# ADC.net
KiCad netlist of a schematic drawn in Altium Designer
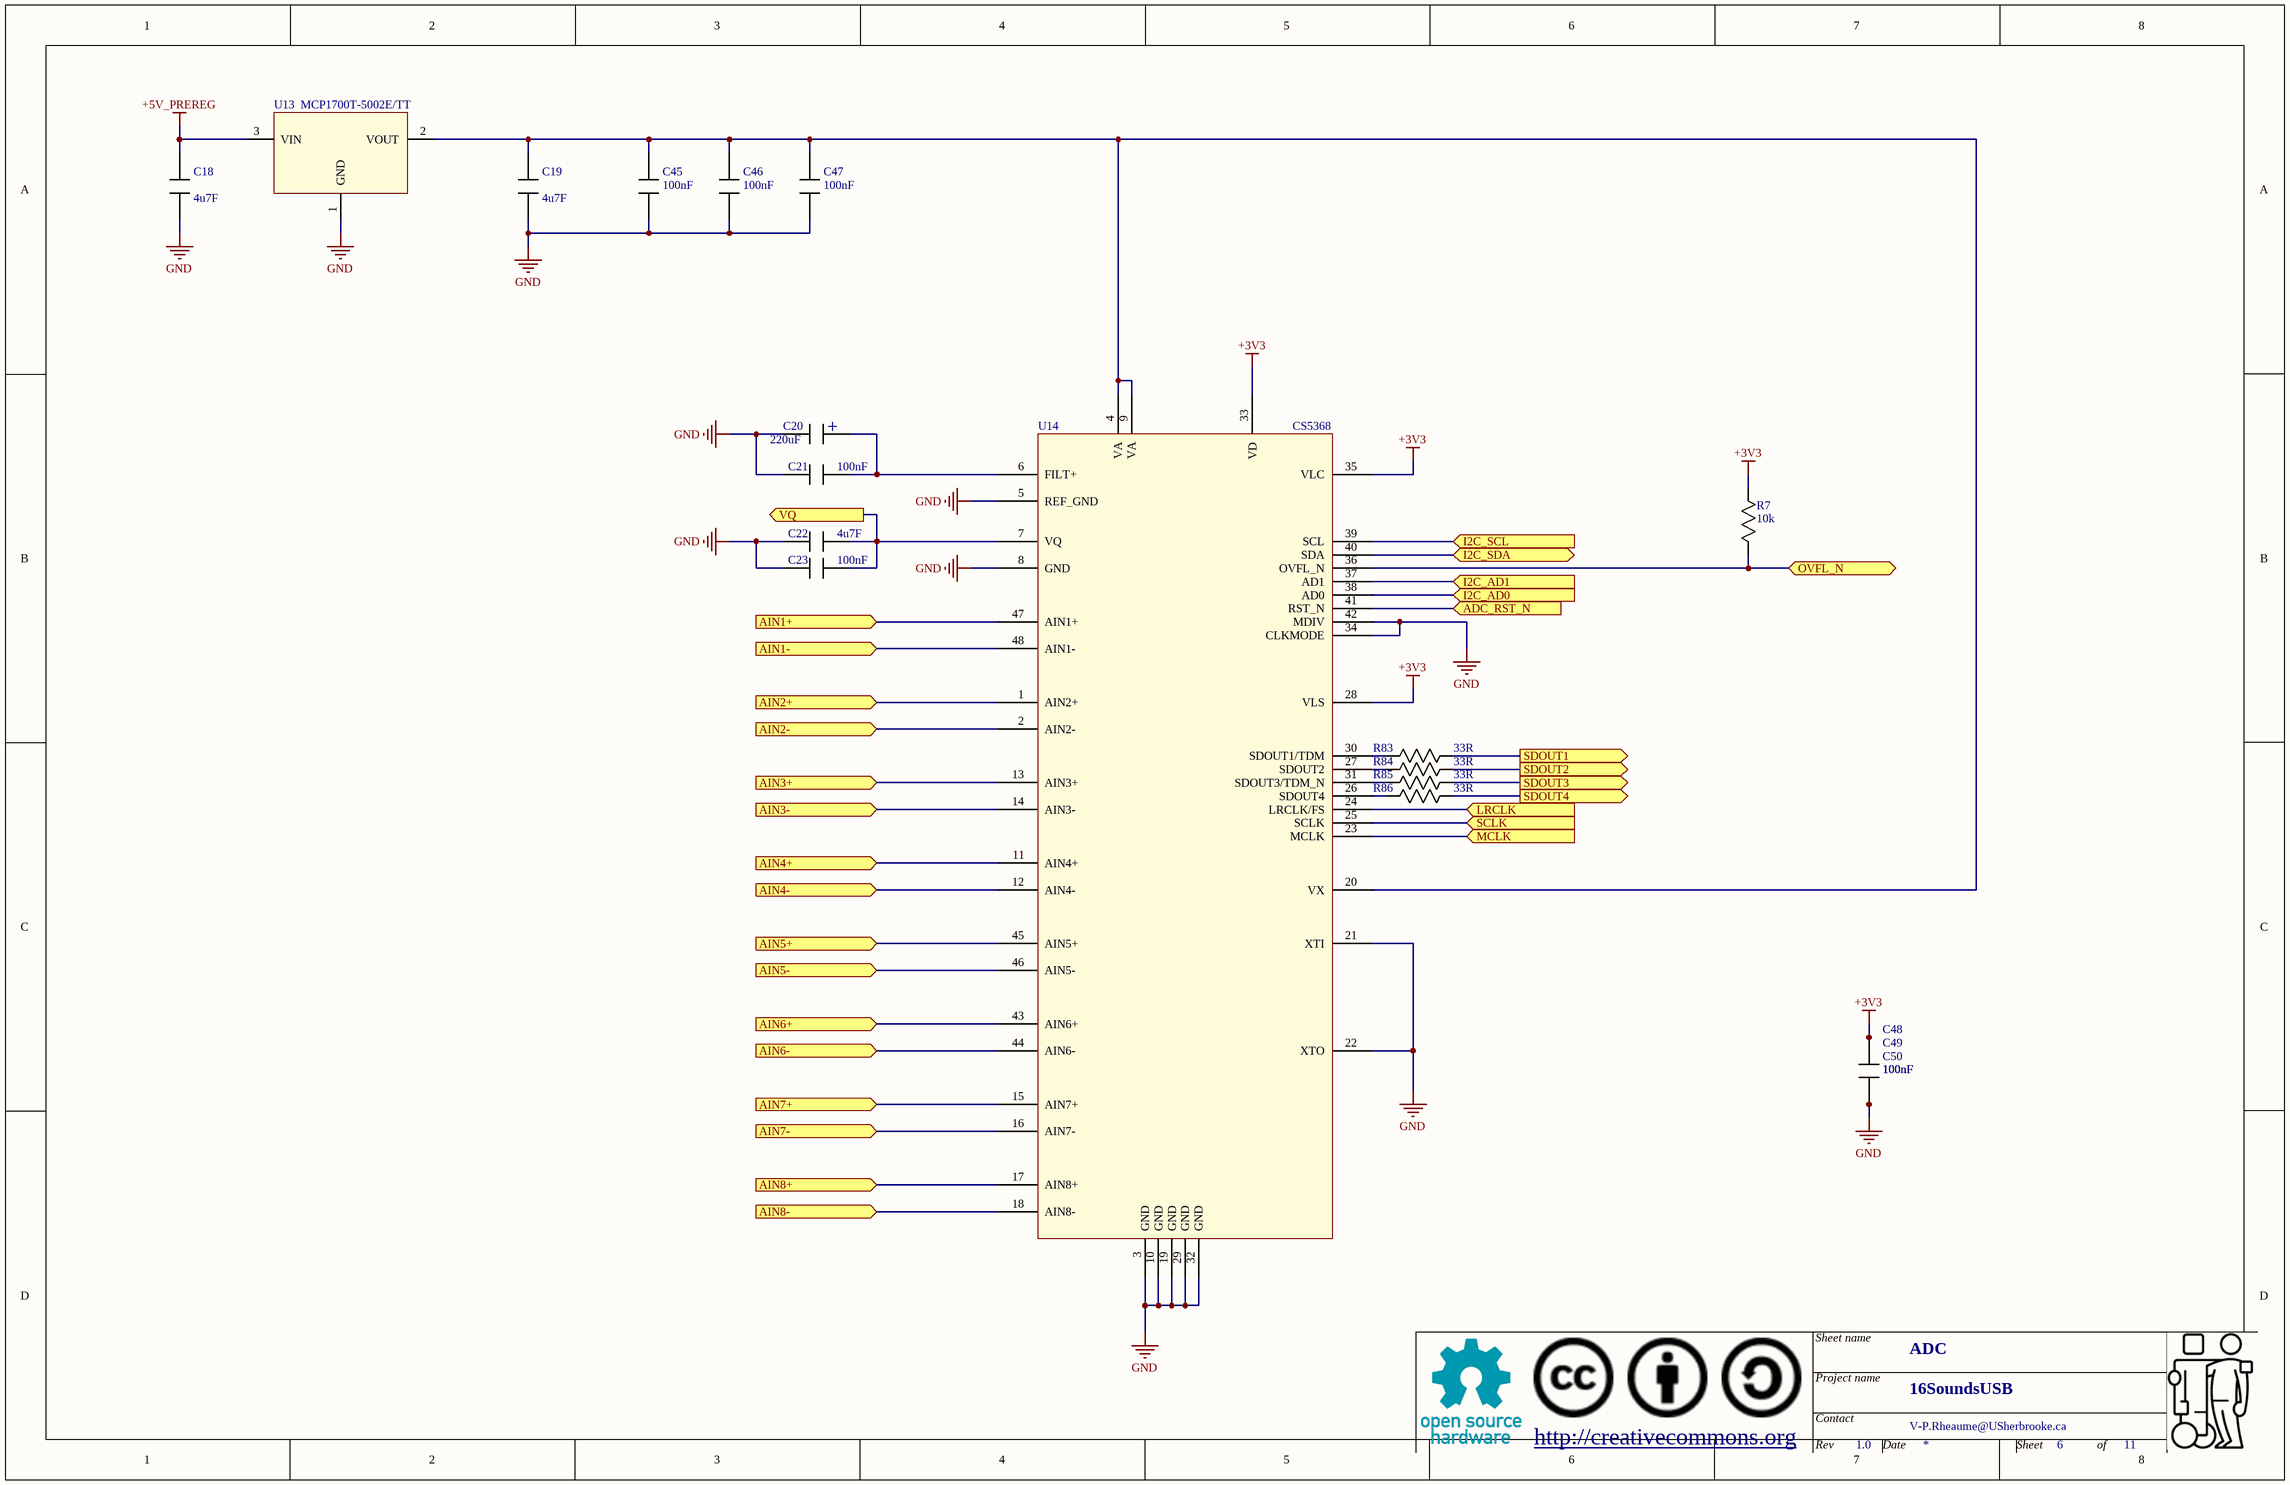
[diagram p0: ADC.SchDoc]

(export (version "E")
  (design (tool "Eeschema 10.0.6"))
  (components
    (comp (ref "C18")
      (value "4u7F")
      (footprint "0805")
      (description "Capacitor")
      (libsource (lib "INTER_2014") (part "Capacitor"))
    )
    (comp (ref "C19")
      (value "4u7F")
      (footprint "0805")
      (description "Capacitor")
      (libsource (lib "INTER_2014") (part "Capacitor"))
    )
    (comp (ref "C20")
      (value "220uF")
      (footprint "CAP_RAD_SMD_DIA315")
      (description "Capacitor")
      (fields (field (name "Comment") "Capacitor_Polarized"))
      (libsource (lib "INTER_2014") (part "Capacitor_Polarized"))
    )
    (comp (ref "C21")
      (value "100nF")
      (footprint "0603")
      (description "Capacitor")
      (libsource (lib "INTER_2014") (part "Capacitor"))
    )
    (comp (ref "C22")
      (value "4u7F")
      (footprint "0805")
      (description "Capacitor")
      (libsource (lib "INTER_2014") (part "Capacitor"))
    )
    (comp (ref "C23")
      (value "100nF")
      (footprint "0603")
      (description "Capacitor")
      (libsource (lib "INTER_2014") (part "Capacitor"))
    )
    (comp (ref "C45")
      (value "100nF")
      (footprint "0603")
      (description "Capacitor")
      (libsource (lib "INTER_2014") (part "Capacitor"))
    )
    (comp (ref "C46")
      (value "100nF")
      (footprint "0603")
      (description "Capacitor")
      (libsource (lib "INTER_2014") (part "Capacitor"))
    )
    (comp (ref "C47")
      (value "100nF")
      (footprint "0603")
      (description "Capacitor")
      (libsource (lib "INTER_2014") (part "Capacitor"))
    )
    (comp (ref "C48")
      (value "100nF")
      (footprint "0603")
      (description "Capacitor")
      (libsource (lib "INTER_2014") (part "Capacitor"))
    )
    (comp (ref "C49")
      (value "100nF")
      (footprint "0603")
      (description "Capacitor")
      (libsource (lib "INTER_2014") (part "Capacitor"))
    )
    (comp (ref "C50")
      (value "100nF")
      (footprint "0603")
      (description "Capacitor")
      (libsource (lib "INTER_2014") (part "Capacitor"))
    )
    (comp (ref "R7")
      (value "10k")
      (footprint "0603")
      (description "Resistor")
      (libsource (lib "INTER_2014") (part "Resistor"))
    )
    (comp (ref "R83")
      (value "33R")
      (footprint "0603")
      (description "Resistor")
      (libsource (lib "INTER_2014") (part "Resistor"))
    )
    (comp (ref "R84")
      (value "33R")
      (footprint "0603")
      (description "Resistor")
      (libsource (lib "INTER_2014") (part "Resistor"))
    )
    (comp (ref "R85")
      (value "33R")
      (footprint "0603")
      (description "Resistor")
      (libsource (lib "INTER_2014") (part "Resistor"))
    )
    (comp (ref "R86")
      (value "33R")
      (footprint "0603")
      (description "Resistor")
      (libsource (lib "INTER_2014") (part "Resistor"))
    )
    (comp (ref "U13")
      (value "MCP1700")
      (footprint "SOT23_132")
      (description "Linear voltage regulator")
      (fields (field (name "MFG") "Microchip") (field (name "MFG_PN") "MCP1700T-5002E/TT"))
      (libsource (lib "INTER_2014") (part "MCP1700"))
    )
    (comp (ref "U14")
      (value "CS5368")
      (footprint "LQFP_48L_CIRRUS")
      (description "ADC, 24bit, 8 chan, 192kHz, PCM, TDM, LQFP48")
      (fields (field (name "MFG") "Cirrus"))
      (libsource (lib "INTER_2014") (part "CS5368"))
    )
  )
  (nets
    (net (code "1") (name "+3V3") (class "Default")
      (node (ref "C48") (pin "1") (pintype "passive"))
      (node (ref "C49") (pin "1") (pintype "passive"))
      (node (ref "C50") (pin "1") (pintype "passive"))
      (node (ref "R7") (pin "1") (pintype "passive"))
      (node (ref "U14") (pin "28") (pinfunction "VLS_28") (pintype "passive"))
      (node (ref "U14") (pin "33") (pinfunction "VD_33") (pintype "passive"))
      (node (ref "U14") (pin "35") (pinfunction "VLC_35") (pintype "passive"))
    )
    (net (code "2") (name "+5V_PREREG") (class "Default")
      (node (ref "C18") (pin "1") (pintype "passive"))
      (node (ref "U13") (pin "3") (pinfunction "VIN_3") (pintype "passive"))
    )
    (net (code "3") (name "/ADC_RST_N") (class "Default")
      (node (ref "U14") (pin "41") (pinfunction "RST_N_41") (pintype "passive"))
    )
    (net (code "4") (name "/AIN1+") (class "Default")
      (node (ref "U14") (pin "47") (pinfunction "AIN1+_47") (pintype "passive"))
    )
    (net (code "5") (name "/AIN1-") (class "Default")
      (node (ref "U14") (pin "48") (pinfunction "AIN1-_48") (pintype "passive"))
    )
    (net (code "6") (name "/AIN2+") (class "Default")
      (node (ref "U14") (pin "1") (pinfunction "AIN2+_1") (pintype "passive"))
    )
    (net (code "7") (name "/AIN2-") (class "Default")
      (node (ref "U14") (pin "2") (pinfunction "AIN2-_2") (pintype "passive"))
    )
    (net (code "8") (name "/AIN3+") (class "Default")
      (node (ref "U14") (pin "13") (pinfunction "AIN3+_13") (pintype "passive"))
    )
    (net (code "9") (name "/AIN3-") (class "Default")
      (node (ref "U14") (pin "14") (pinfunction "AIN3-_14") (pintype "passive"))
    )
    (net (code "10") (name "/AIN4+") (class "Default")
      (node (ref "U14") (pin "11") (pinfunction "AIN4+_11") (pintype "passive"))
    )
    (net (code "11") (name "/AIN4-") (class "Default")
      (node (ref "U14") (pin "12") (pinfunction "AIN4-_12") (pintype "passive"))
    )
    (net (code "12") (name "/AIN5+") (class "Default")
      (node (ref "U14") (pin "45") (pinfunction "AIN5+_45") (pintype "passive"))
    )
    (net (code "13") (name "/AIN5-") (class "Default")
      (node (ref "U14") (pin "46") (pinfunction "AIN5-_46") (pintype "passive"))
    )
    (net (code "14") (name "/AIN6+") (class "Default")
      (node (ref "U14") (pin "43") (pinfunction "AIN6+_43") (pintype "passive"))
    )
    (net (code "15") (name "/AIN6-") (class "Default")
      (node (ref "U14") (pin "44") (pinfunction "AIN6-_44") (pintype "passive"))
    )
    (net (code "16") (name "/AIN7+") (class "Default")
      (node (ref "U14") (pin "15") (pinfunction "AIN7+_15") (pintype "passive"))
    )
    (net (code "17") (name "/AIN7-") (class "Default")
      (node (ref "U14") (pin "16") (pinfunction "AIN7-_16") (pintype "passive"))
    )
    (net (code "18") (name "/AIN8+") (class "Default")
      (node (ref "U14") (pin "17") (pinfunction "AIN8+_17") (pintype "passive"))
    )
    (net (code "19") (name "/AIN8-") (class "Default")
      (node (ref "U14") (pin "18") (pinfunction "AIN8-_18") (pintype "passive"))
    )
    (net (code "20") (name "/I2C_AD0") (class "Default")
      (node (ref "U14") (pin "38") (pinfunction "AD0_38") (pintype "passive"))
    )
    (net (code "21") (name "/I2C_AD1") (class "Default")
      (node (ref "U14") (pin "37") (pinfunction "AD1_37") (pintype "passive"))
    )
    (net (code "22") (name "/I2C_SCL") (class "Default")
      (node (ref "U14") (pin "39") (pinfunction "SCL_39") (pintype "passive"))
    )
    (net (code "23") (name "/I2C_SDA") (class "Default")
      (node (ref "U14") (pin "40") (pinfunction "SDA_40") (pintype "passive"))
    )
    (net (code "24") (name "/LRCLK") (class "Default")
      (node (ref "U14") (pin "24") (pinfunction "LRCLK/FS_24") (pintype "passive"))
    )
    (net (code "25") (name "/MCLK") (class "Default")
      (node (ref "U14") (pin "23") (pinfunction "MCLK_23") (pintype "passive"))
    )
    (net (code "26") (name "/OVFL_N") (class "Default")
      (node (ref "R7") (pin "2") (pintype "passive"))
      (node (ref "U14") (pin "36") (pinfunction "OVFL_N_36") (pintype "passive"))
    )
    (net (code "27") (name "/SCLK") (class "Default")
      (node (ref "U14") (pin "25") (pinfunction "SCLK_25") (pintype "passive"))
    )
    (net (code "28") (name "/SDOUT1") (class "Default") (node (ref "R83") (pin "2") (pintype "passive")))
    (net (code "29") (name "/SDOUT2") (class "Default") (node (ref "R84") (pin "2") (pintype "passive")))
    (net (code "30") (name "/SDOUT3") (class "Default") (node (ref "R85") (pin "2") (pintype "passive")))
    (net (code "31") (name "/SDOUT4") (class "Default") (node (ref "R86") (pin "2") (pintype "passive")))
    (net (code "32") (name "/VQ") (class "Default")
      (node (ref "C22") (pin "1") (pintype "passive"))
      (node (ref "C23") (pin "1") (pintype "passive"))
      (node (ref "U14") (pin "7") (pinfunction "VQ_7") (pintype "passive"))
    )
    (net (code "33") (name "GND") (class "Default")
      (node (ref "C18") (pin "2") (pintype "passive"))
      (node (ref "C19") (pin "2") (pintype "passive"))
      (node (ref "C20") (pin "-") (pintype "passive"))
      (node (ref "C21") (pin "2") (pintype "passive"))
      (node (ref "C22") (pin "2") (pintype "passive"))
      (node (ref "C23") (pin "2") (pintype "passive"))
      (node (ref "C45") (pin "2") (pintype "passive"))
      (node (ref "C46") (pin "2") (pintype "passive"))
      (node (ref "C47") (pin "2") (pintype "passive"))
      (node (ref "C48") (pin "2") (pintype "passive"))
      (node (ref "C49") (pin "2") (pintype "passive"))
      (node (ref "C50") (pin "2") (pintype "passive"))
      (node (ref "U13") (pin "1") (pinfunction "GND_1") (pintype "passive"))
      (node (ref "U14") (pin "10") (pinfunction "GND_10") (pintype "passive"))
      (node (ref "U14") (pin "19") (pinfunction "GND_19") (pintype "passive"))
      (node (ref "U14") (pin "21") (pinfunction "XTI_21") (pintype "passive"))
      (node (ref "U14") (pin "22") (pinfunction "XTO_22") (pintype "passive"))
      (node (ref "U14") (pin "29") (pinfunction "GND_29") (pintype "passive"))
      (node (ref "U14") (pin "3") (pinfunction "GND_3") (pintype "passive"))
      (node (ref "U14") (pin "32") (pinfunction "GND_32") (pintype "passive"))
      (node (ref "U14") (pin "34") (pinfunction "CLKMODE_34") (pintype "passive"))
      (node (ref "U14") (pin "42") (pinfunction "MDIV_42") (pintype "passive"))
      (node (ref "U14") (pin "5") (pinfunction "REF_GND_5") (pintype "passive"))
      (node (ref "U14") (pin "8") (pinfunction "GND_8") (pintype "passive"))
    )
    (net (code "34") (name "Net-(U13-VOUT)") (class "Default")
      (node (ref "C19") (pin "1") (pintype "passive"))
      (node (ref "C45") (pin "1") (pintype "passive"))
      (node (ref "C46") (pin "1") (pintype "passive"))
      (node (ref "C47") (pin "1") (pintype "passive"))
      (node (ref "U13") (pin "2") (pinfunction "VOUT_2") (pintype "passive"))
      (node (ref "U14") (pin "20") (pinfunction "VX_20") (pintype "passive"))
      (node (ref "U14") (pin "4") (pinfunction "VA_4") (pintype "passive"))
      (node (ref "U14") (pin "9") (pinfunction "VA_9") (pintype "passive"))
    )
    (net (code "35") (name "Net-(U14-FILT+)") (class "Default")
      (node (ref "C20") (pin "+") (pintype "passive"))
      (node (ref "C21") (pin "1") (pintype "passive"))
      (node (ref "U14") (pin "6") (pinfunction "FILT+_6") (pintype "passive"))
    )
    (net (code "36") (name "Net-(U14-SDOUT1{slash}TDM)") (class "Default")
      (node (ref "R83") (pin "1") (pintype "passive"))
      (node (ref "U14") (pin "30") (pinfunction "SDOUT1/TDM_30") (pintype "passive"))
    )
    (net (code "37") (name "Net-(U14-SDOUT2)") (class "Default")
      (node (ref "R84") (pin "1") (pintype "passive"))
      (node (ref "U14") (pin "27") (pinfunction "SDOUT2_27") (pintype "passive"))
    )
    (net (code "38") (name "Net-(U14-SDOUT3{slash}TDM_N)") (class "Default")
      (node (ref "R85") (pin "1") (pintype "passive"))
      (node (ref "U14") (pin "31") (pinfunction "SDOUT3/TDM_N_31") (pintype "passive"))
    )
    (net (code "39") (name "Net-(U14-SDOUT4)") (class "Default")
      (node (ref "R86") (pin "1") (pintype "passive"))
      (node (ref "U14") (pin "26") (pinfunction "SDOUT4_26") (pintype "passive"))
    )
  )
)
